# Main.net
KiCad netlist of a schematic drawn in Altium Designer
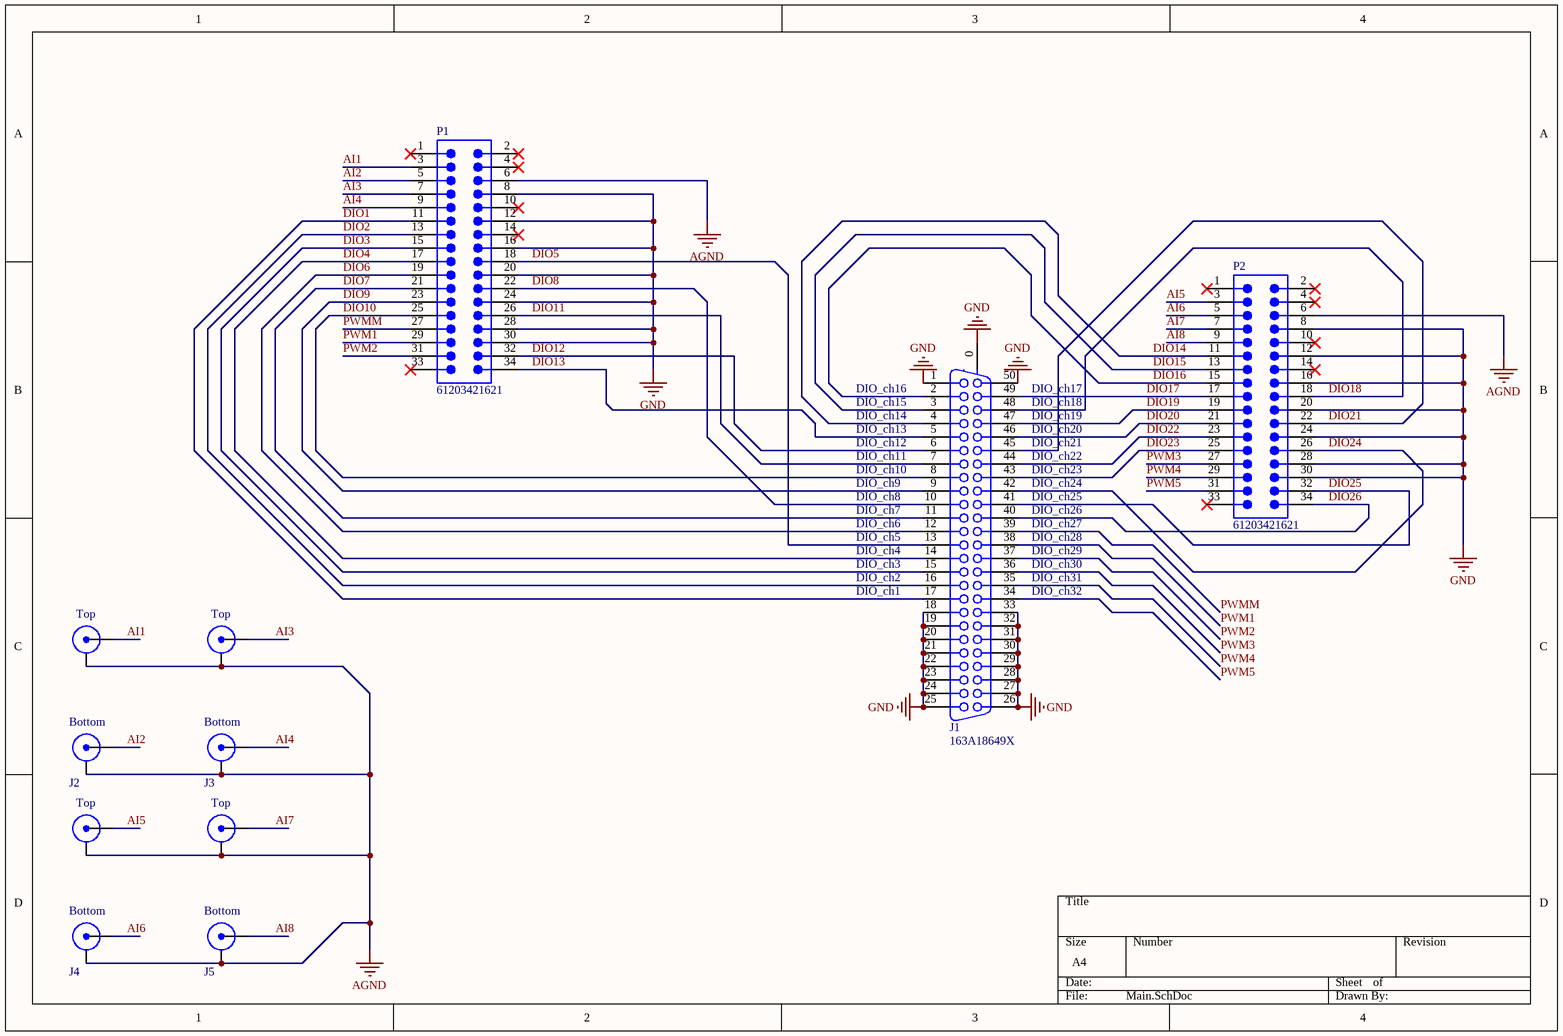
[diagram p0: Main.SchDoc]

(export (version "E")
  (design (tool "Eeschema 10.0.6"))
  (components
    (comp (ref "J1")
      (value "163A18649X")
      (footprint "CON D STD 50Way Male RA")
      (description "50 Position D-Sub Plug, Male Pins Connector")
      (libsource (lib "LDCN Components") (part "CON DSUB50 RA Male"))
    )
    (comp (ref "J2")
      (value "CON BNC Dual B")
      (footprint "AndrewsPCB:BNC_INS90_Dual")
      (description "BNC Dual - Black")
      (fields (field (name "MANUFACTURER") "Amphenol"))
      (libsource (lib "AndrewsSCH") (part "CON BNC Dual B"))
    )
    (comp (ref "J3")
      (value "CON BNC Dual B")
      (footprint "AndrewsPCB:BNC_INS90_Dual")
      (description "BNC Dual - Black")
      (fields (field (name "MANUFACTURER") "Amphenol"))
      (libsource (lib "AndrewsSCH") (part "CON BNC Dual B"))
    )
    (comp (ref "J4")
      (value "CON BNC Dual B")
      (footprint "AndrewsPCB:BNC_INS90_Dual")
      (description "BNC Dual - Black")
      (fields (field (name "MANUFACTURER") "Amphenol"))
      (libsource (lib "AndrewsSCH") (part "CON BNC Dual B"))
    )
    (comp (ref "J5")
      (value "CON BNC Dual B")
      (footprint "AndrewsPCB:BNC_INS90_Dual")
      (description "BNC Dual - Black")
      (fields (field (name "MANUFACTURER") "Amphenol"))
      (libsource (lib "AndrewsSCH") (part "CON BNC Dual B"))
    )
    (comp (ref "P1")
      (value "61203421621")
      (footprint "61203421621")
      (libsource (lib "Altium Content Vault") (part "Header_Male_2R_34P"))
    )
    (comp (ref "P2")
      (value "61203421621")
      (footprint "61203421621")
      (libsource (lib "Altium Content Vault") (part "Header_Male_2R_34P"))
    )
  )
  (nets
    (net (code "1") (name "/AI1") (class "Default")
      (node (ref "J2") (pin "3") (pinfunction "3_3") (pintype "passive"))
      (node (ref "P1") (pin "3") (pinfunction "3_3") (pintype "passive"))
    )
    (net (code "2") (name "/AI2") (class "Default")
      (node (ref "J2") (pin "1") (pinfunction "1_1") (pintype "passive"))
      (node (ref "P1") (pin "5") (pinfunction "5_5") (pintype "passive"))
    )
    (net (code "3") (name "/AI3") (class "Default")
      (node (ref "J3") (pin "3") (pinfunction "3_3") (pintype "passive"))
      (node (ref "P1") (pin "7") (pinfunction "7_7") (pintype "passive"))
    )
    (net (code "4") (name "/AI4") (class "Default")
      (node (ref "J3") (pin "1") (pinfunction "1_1") (pintype "passive"))
      (node (ref "P1") (pin "9") (pinfunction "9_9") (pintype "passive"))
    )
    (net (code "5") (name "/AI5") (class "Default")
      (node (ref "J4") (pin "3") (pinfunction "3_3") (pintype "passive"))
      (node (ref "P2") (pin "3") (pinfunction "3_3") (pintype "passive"))
    )
    (net (code "6") (name "/AI6") (class "Default")
      (node (ref "J4") (pin "1") (pinfunction "1_1") (pintype "passive"))
      (node (ref "P2") (pin "5") (pinfunction "5_5") (pintype "passive"))
    )
    (net (code "7") (name "/AI7") (class "Default")
      (node (ref "J5") (pin "3") (pinfunction "3_3") (pintype "passive"))
      (node (ref "P2") (pin "7") (pinfunction "7_7") (pintype "passive"))
    )
    (net (code "8") (name "/AI8") (class "Default")
      (node (ref "J5") (pin "1") (pinfunction "1_1") (pintype "passive"))
      (node (ref "P2") (pin "9") (pinfunction "9_9") (pintype "passive"))
    )
    (net (code "9") (name "/DIO1") (class "Default")
      (node (ref "J1") (pin "17") (pinfunction "17_17") (pintype "passive"))
      (node (ref "P1") (pin "11") (pinfunction "11_11") (pintype "passive"))
    )
    (net (code "10") (name "/DIO2") (class "Default")
      (node (ref "J1") (pin "16") (pinfunction "16_16") (pintype "passive"))
      (node (ref "P1") (pin "13") (pinfunction "13_13") (pintype "passive"))
    )
    (net (code "11") (name "/DIO3") (class "Default")
      (node (ref "J1") (pin "15") (pinfunction "15_15") (pintype "passive"))
      (node (ref "P1") (pin "15") (pinfunction "15_15") (pintype "passive"))
    )
    (net (code "12") (name "/DIO4") (class "Default")
      (node (ref "J1") (pin "14") (pinfunction "14_14") (pintype "passive"))
      (node (ref "P1") (pin "17") (pinfunction "17_17") (pintype "passive"))
    )
    (net (code "13") (name "/DIO5") (class "Default")
      (node (ref "J1") (pin "13") (pinfunction "13_13") (pintype "passive"))
      (node (ref "P1") (pin "18") (pinfunction "18_18") (pintype "passive"))
    )
    (net (code "14") (name "/DIO6") (class "Default")
      (node (ref "J1") (pin "12") (pinfunction "12_12") (pintype "passive"))
      (node (ref "P1") (pin "19") (pinfunction "19_19") (pintype "passive"))
    )
    (net (code "15") (name "/DIO7") (class "Default")
      (node (ref "J1") (pin "11") (pinfunction "11_11") (pintype "passive"))
      (node (ref "P1") (pin "21") (pinfunction "21_21") (pintype "passive"))
    )
    (net (code "16") (name "/DIO8") (class "Default")
      (node (ref "J1") (pin "10") (pinfunction "10_10") (pintype "passive"))
      (node (ref "P1") (pin "22") (pinfunction "22_22") (pintype "passive"))
    )
    (net (code "17") (name "/DIO9") (class "Default")
      (node (ref "J1") (pin "9") (pinfunction "9_9") (pintype "passive"))
      (node (ref "P1") (pin "23") (pinfunction "23_23") (pintype "passive"))
    )
    (net (code "18") (name "/DIO10") (class "Default")
      (node (ref "J1") (pin "8") (pinfunction "8_8") (pintype "passive"))
      (node (ref "P1") (pin "25") (pinfunction "25_25") (pintype "passive"))
    )
    (net (code "19") (name "/DIO11") (class "Default")
      (node (ref "J1") (pin "7") (pinfunction "7_7") (pintype "passive"))
      (node (ref "P1") (pin "26") (pinfunction "26_26") (pintype "passive"))
    )
    (net (code "20") (name "/DIO12") (class "Default")
      (node (ref "J1") (pin "6") (pinfunction "6_6") (pintype "passive"))
      (node (ref "P1") (pin "32") (pinfunction "32_32") (pintype "passive"))
    )
    (net (code "21") (name "/DIO13") (class "Default")
      (node (ref "J1") (pin "5") (pinfunction "5_5") (pintype "passive"))
      (node (ref "P1") (pin "34") (pinfunction "34_34") (pintype "passive"))
    )
    (net (code "22") (name "/DIO14") (class "Default")
      (node (ref "J1") (pin "4") (pinfunction "4_4") (pintype "passive"))
      (node (ref "P2") (pin "11") (pinfunction "11_11") (pintype "passive"))
    )
    (net (code "23") (name "/DIO15") (class "Default")
      (node (ref "J1") (pin "3") (pinfunction "3_3") (pintype "passive"))
      (node (ref "P2") (pin "13") (pinfunction "13_13") (pintype "passive"))
    )
    (net (code "24") (name "/DIO16") (class "Default")
      (node (ref "J1") (pin "2") (pinfunction "2_2") (pintype "passive"))
      (node (ref "P2") (pin "15") (pinfunction "15_15") (pintype "passive"))
    )
    (net (code "25") (name "/DIO17") (class "Default")
      (node (ref "J1") (pin "49") (pinfunction "49_49") (pintype "passive"))
      (node (ref "P2") (pin "17") (pinfunction "17_17") (pintype "passive"))
    )
    (net (code "26") (name "/DIO18") (class "Default")
      (node (ref "J1") (pin "48") (pinfunction "48_48") (pintype "passive"))
      (node (ref "P2") (pin "18") (pinfunction "18_18") (pintype "passive"))
    )
    (net (code "27") (name "/DIO19") (class "Default")
      (node (ref "J1") (pin "47") (pinfunction "47_47") (pintype "passive"))
      (node (ref "P2") (pin "19") (pinfunction "19_19") (pintype "passive"))
    )
    (net (code "28") (name "/DIO20") (class "Default")
      (node (ref "J1") (pin "46") (pinfunction "46_46") (pintype "passive"))
      (node (ref "P2") (pin "21") (pinfunction "21_21") (pintype "passive"))
    )
    (net (code "29") (name "/DIO21") (class "Default")
      (node (ref "J1") (pin "45") (pinfunction "45_45") (pintype "passive"))
      (node (ref "P2") (pin "22") (pinfunction "22_22") (pintype "passive"))
    )
    (net (code "30") (name "/DIO22") (class "Default")
      (node (ref "J1") (pin "44") (pinfunction "44_44") (pintype "passive"))
      (node (ref "P2") (pin "23") (pinfunction "23_23") (pintype "passive"))
    )
    (net (code "31") (name "/DIO23") (class "Default")
      (node (ref "J1") (pin "43") (pinfunction "43_43") (pintype "passive"))
      (node (ref "P2") (pin "25") (pinfunction "25_25") (pintype "passive"))
    )
    (net (code "32") (name "/DIO24") (class "Default")
      (node (ref "J1") (pin "42") (pinfunction "42_42") (pintype "passive"))
      (node (ref "P2") (pin "26") (pinfunction "26_26") (pintype "passive"))
    )
    (net (code "33") (name "/DIO25") (class "Default")
      (node (ref "J1") (pin "41") (pinfunction "41_41") (pintype "passive"))
      (node (ref "P2") (pin "32") (pinfunction "32_32") (pintype "passive"))
    )
    (net (code "34") (name "/DIO26") (class "Default")
      (node (ref "J1") (pin "40") (pinfunction "40_40") (pintype "passive"))
      (node (ref "P2") (pin "34") (pinfunction "34_34") (pintype "passive"))
    )
    (net (code "35") (name "/PWM1") (class "Default")
      (node (ref "J1") (pin "38") (pinfunction "38_38") (pintype "passive"))
      (node (ref "P1") (pin "29") (pinfunction "29_29") (pintype "passive"))
    )
    (net (code "36") (name "/PWM2") (class "Default")
      (node (ref "J1") (pin "37") (pinfunction "37_37") (pintype "passive"))
      (node (ref "P1") (pin "31") (pinfunction "31_31") (pintype "passive"))
    )
    (net (code "37") (name "/PWM3") (class "Default")
      (node (ref "J1") (pin "36") (pinfunction "36_36") (pintype "passive"))
      (node (ref "P2") (pin "27") (pinfunction "27_27") (pintype "passive"))
    )
    (net (code "38") (name "/PWM4") (class "Default")
      (node (ref "J1") (pin "35") (pinfunction "35_35") (pintype "passive"))
      (node (ref "P2") (pin "29") (pinfunction "29_29") (pintype "passive"))
    )
    (net (code "39") (name "/PWM5") (class "Default")
      (node (ref "J1") (pin "34") (pinfunction "34_34") (pintype "passive"))
      (node (ref "P2") (pin "31") (pinfunction "31_31") (pintype "passive"))
    )
    (net (code "40") (name "/PWMM") (class "Default")
      (node (ref "J1") (pin "39") (pinfunction "39_39") (pintype "passive"))
      (node (ref "P1") (pin "27") (pinfunction "27_27") (pintype "passive"))
    )
    (net (code "41") (name "AGND") (class "Default")
      (node (ref "J2") (pin "2") (pinfunction "2_2") (pintype "passive"))
      (node (ref "J2") (pin "4") (pinfunction "4_4") (pintype "passive"))
      (node (ref "J3") (pin "2") (pinfunction "2_2") (pintype "passive"))
      (node (ref "J3") (pin "4") (pinfunction "4_4") (pintype "passive"))
      (node (ref "J4") (pin "2") (pinfunction "2_2") (pintype "passive"))
      (node (ref "J4") (pin "4") (pinfunction "4_4") (pintype "passive"))
      (node (ref "J5") (pin "2") (pinfunction "2_2") (pintype "passive"))
      (node (ref "J5") (pin "4") (pinfunction "4_4") (pintype "passive"))
      (node (ref "P1") (pin "6") (pinfunction "6_6") (pintype "passive"))
      (node (ref "P2") (pin "6") (pinfunction "6_6") (pintype "passive"))
    )
    (net (code "42") (name "GND") (class "Default")
      (node (ref "J1") (pin "0") (pinfunction "MH1_0") (pintype "passive"))
      (node (ref "J1") (pin "1") (pinfunction "1_1") (pintype "passive"))
      (node (ref "J1") (pin "18") (pinfunction "18_18") (pintype "passive"))
      (node (ref "J1") (pin "19") (pinfunction "19_19") (pintype "passive"))
      (node (ref "J1") (pin "20") (pinfunction "20_20") (pintype "passive"))
      (node (ref "J1") (pin "21") (pinfunction "21_21") (pintype "passive"))
      (node (ref "J1") (pin "22") (pinfunction "22_22") (pintype "passive"))
      (node (ref "J1") (pin "23") (pinfunction "23_23") (pintype "passive"))
      (node (ref "J1") (pin "24") (pinfunction "24_24") (pintype "passive"))
      (node (ref "J1") (pin "25") (pinfunction "25_25") (pintype "passive"))
      (node (ref "J1") (pin "26") (pinfunction "26_26") (pintype "passive"))
      (node (ref "J1") (pin "27") (pinfunction "27_27") (pintype "passive"))
      (node (ref "J1") (pin "28") (pinfunction "28_28") (pintype "passive"))
      (node (ref "J1") (pin "29") (pinfunction "29_29") (pintype "passive"))
      (node (ref "J1") (pin "30") (pinfunction "30_30") (pintype "passive"))
      (node (ref "J1") (pin "31") (pinfunction "31_31") (pintype "passive"))
      (node (ref "J1") (pin "32") (pinfunction "32_32") (pintype "passive"))
      (node (ref "J1") (pin "33") (pinfunction "33_33") (pintype "passive"))
      (node (ref "J1") (pin "50") (pinfunction "50_50") (pintype "passive"))
      (node (ref "P1") (pin "12") (pinfunction "12_12") (pintype "passive"))
      (node (ref "P1") (pin "16") (pinfunction "16_16") (pintype "passive"))
      (node (ref "P1") (pin "20") (pinfunction "20_20") (pintype "passive"))
      (node (ref "P1") (pin "24") (pinfunction "24_24") (pintype "passive"))
      (node (ref "P1") (pin "28") (pinfunction "28_28") (pintype "passive"))
      (node (ref "P1") (pin "30") (pinfunction "30_30") (pintype "passive"))
      (node (ref "P1") (pin "8") (pinfunction "8_8") (pintype "passive"))
      (node (ref "P2") (pin "12") (pinfunction "12_12") (pintype "passive"))
      (node (ref "P2") (pin "16") (pinfunction "16_16") (pintype "passive"))
      (node (ref "P2") (pin "20") (pinfunction "20_20") (pintype "passive"))
      (node (ref "P2") (pin "24") (pinfunction "24_24") (pintype "passive"))
      (node (ref "P2") (pin "28") (pinfunction "28_28") (pintype "passive"))
      (node (ref "P2") (pin "30") (pinfunction "30_30") (pintype "passive"))
      (node (ref "P2") (pin "8") (pinfunction "8_8") (pintype "passive"))
    )
    (net (code "43") (name "unconnected-(P1-Pad1)") (class "Default")
      (node (ref "P1") (pin "1") (pinfunction "1_1") (pintype "passive+no_connect"))
    )
    (net (code "44") (name "unconnected-(P1-Pad2)") (class "Default")
      (node (ref "P1") (pin "2") (pinfunction "2_2") (pintype "passive+no_connect"))
    )
    (net (code "45") (name "unconnected-(P1-Pad4)") (class "Default")
      (node (ref "P1") (pin "4") (pinfunction "4_4") (pintype "passive+no_connect"))
    )
    (net (code "46") (name "unconnected-(P1-Pad10)") (class "Default")
      (node (ref "P1") (pin "10") (pinfunction "10_10") (pintype "passive+no_connect"))
    )
    (net (code "47") (name "unconnected-(P1-Pad14)") (class "Default")
      (node (ref "P1") (pin "14") (pinfunction "14_14") (pintype "passive+no_connect"))
    )
    (net (code "48") (name "unconnected-(P1-Pad33)") (class "Default")
      (node (ref "P1") (pin "33") (pinfunction "33_33") (pintype "passive+no_connect"))
    )
    (net (code "49") (name "unconnected-(P2-Pad1)") (class "Default")
      (node (ref "P2") (pin "1") (pinfunction "1_1") (pintype "passive+no_connect"))
    )
    (net (code "50") (name "unconnected-(P2-Pad2)") (class "Default")
      (node (ref "P2") (pin "2") (pinfunction "2_2") (pintype "passive+no_connect"))
    )
    (net (code "51") (name "unconnected-(P2-Pad4)") (class "Default")
      (node (ref "P2") (pin "4") (pinfunction "4_4") (pintype "passive+no_connect"))
    )
    (net (code "52") (name "unconnected-(P2-Pad10)") (class "Default")
      (node (ref "P2") (pin "10") (pinfunction "10_10") (pintype "passive+no_connect"))
    )
    (net (code "53") (name "unconnected-(P2-Pad14)") (class "Default")
      (node (ref "P2") (pin "14") (pinfunction "14_14") (pintype "passive+no_connect"))
    )
    (net (code "54") (name "unconnected-(P2-Pad33)") (class "Default")
      (node (ref "P2") (pin "33") (pinfunction "33_33") (pintype "passive+no_connect"))
    )
  )
)
